# InkTime_V1.net
KiCad netlist of a schematic drawn in EAGLE
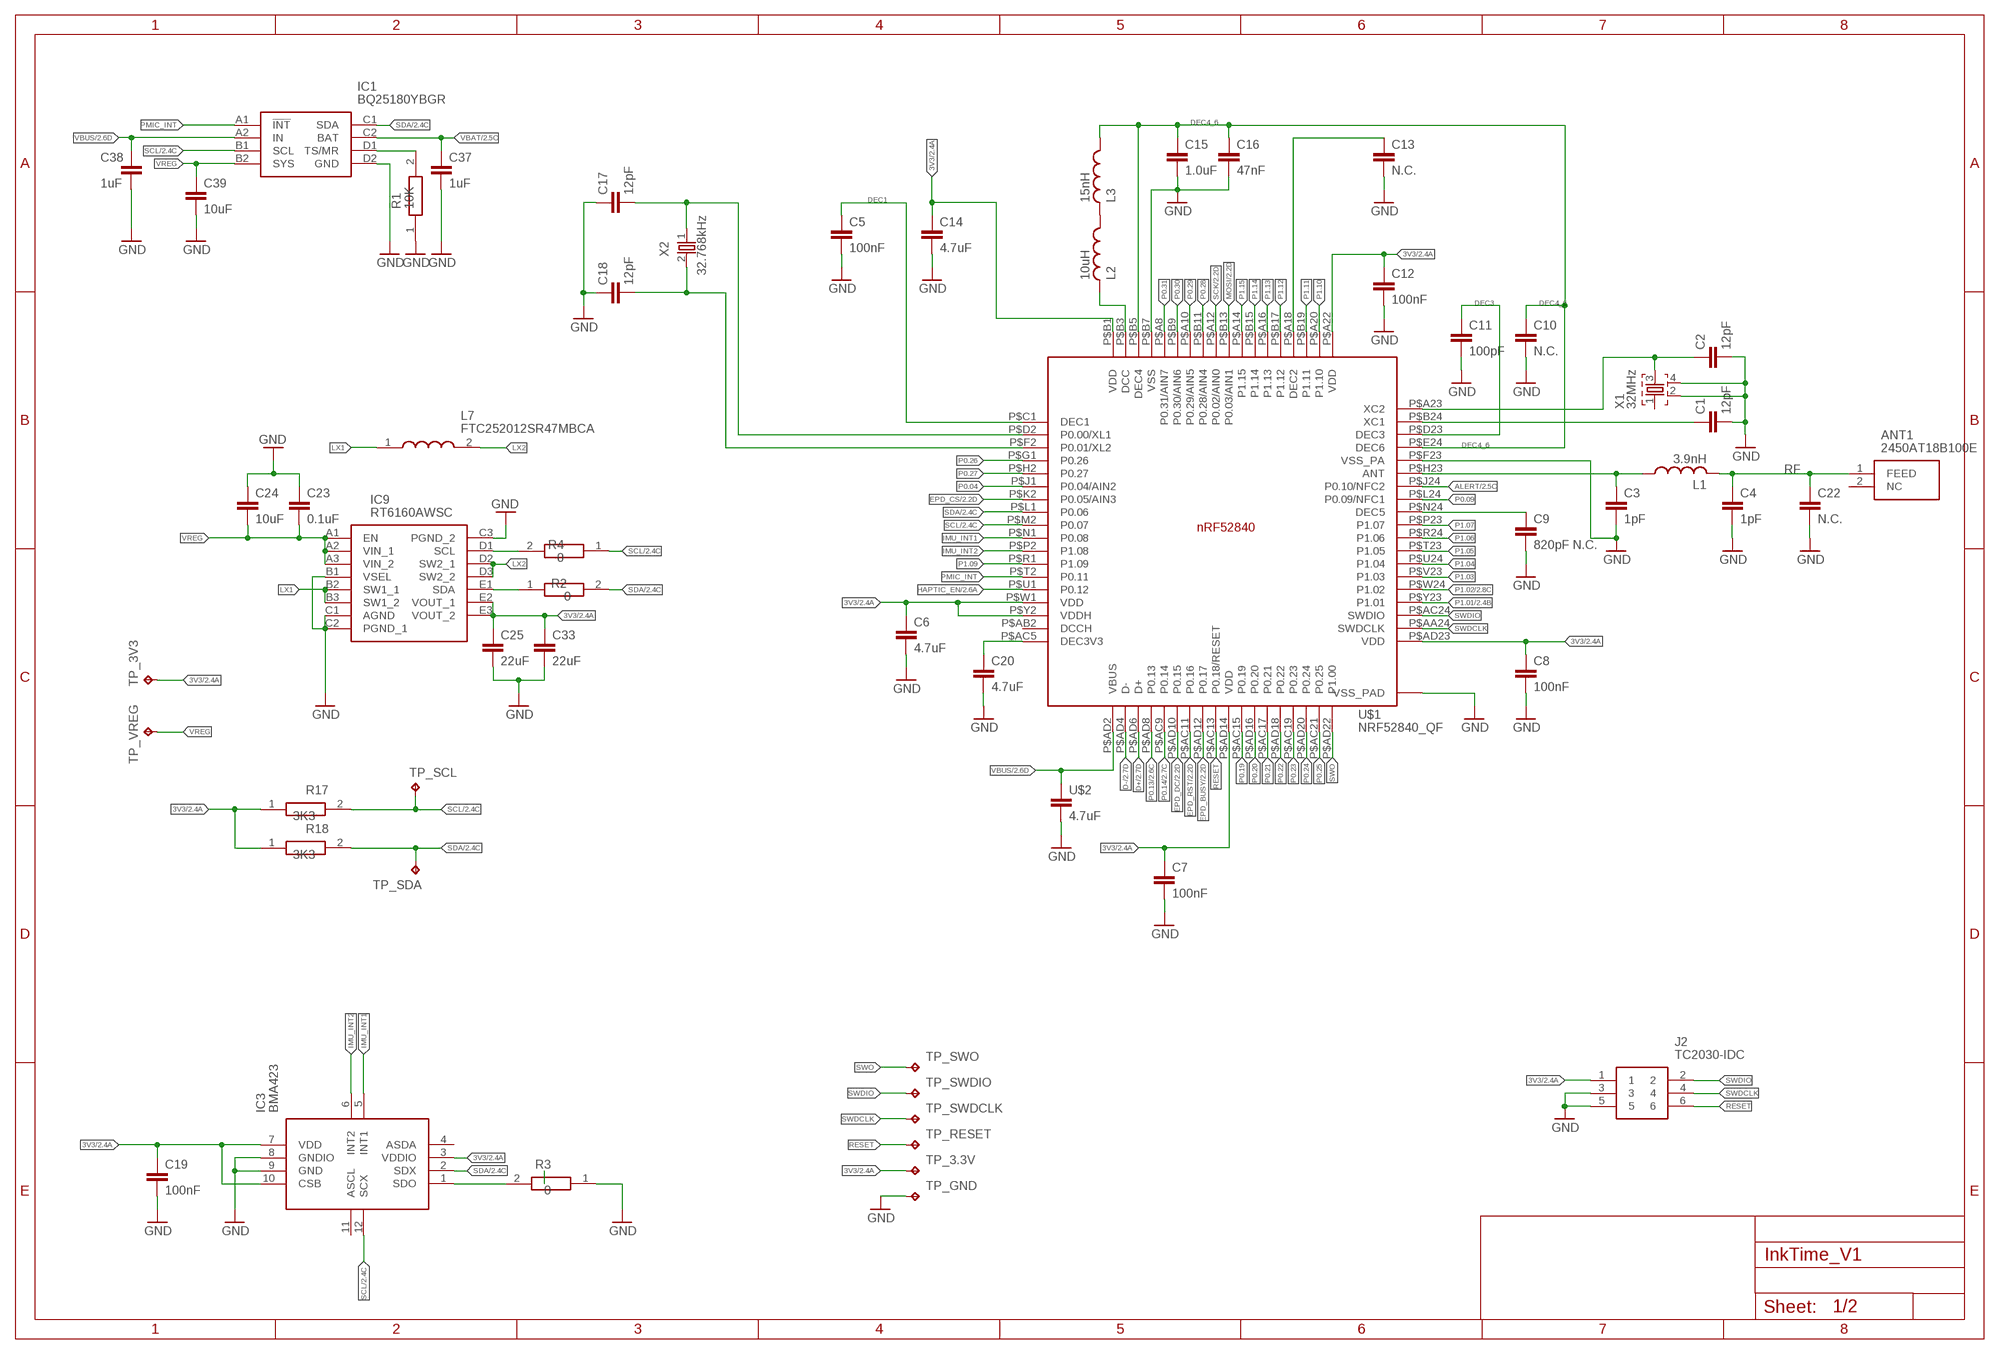
[diagram p0: schematic, sheet 1]
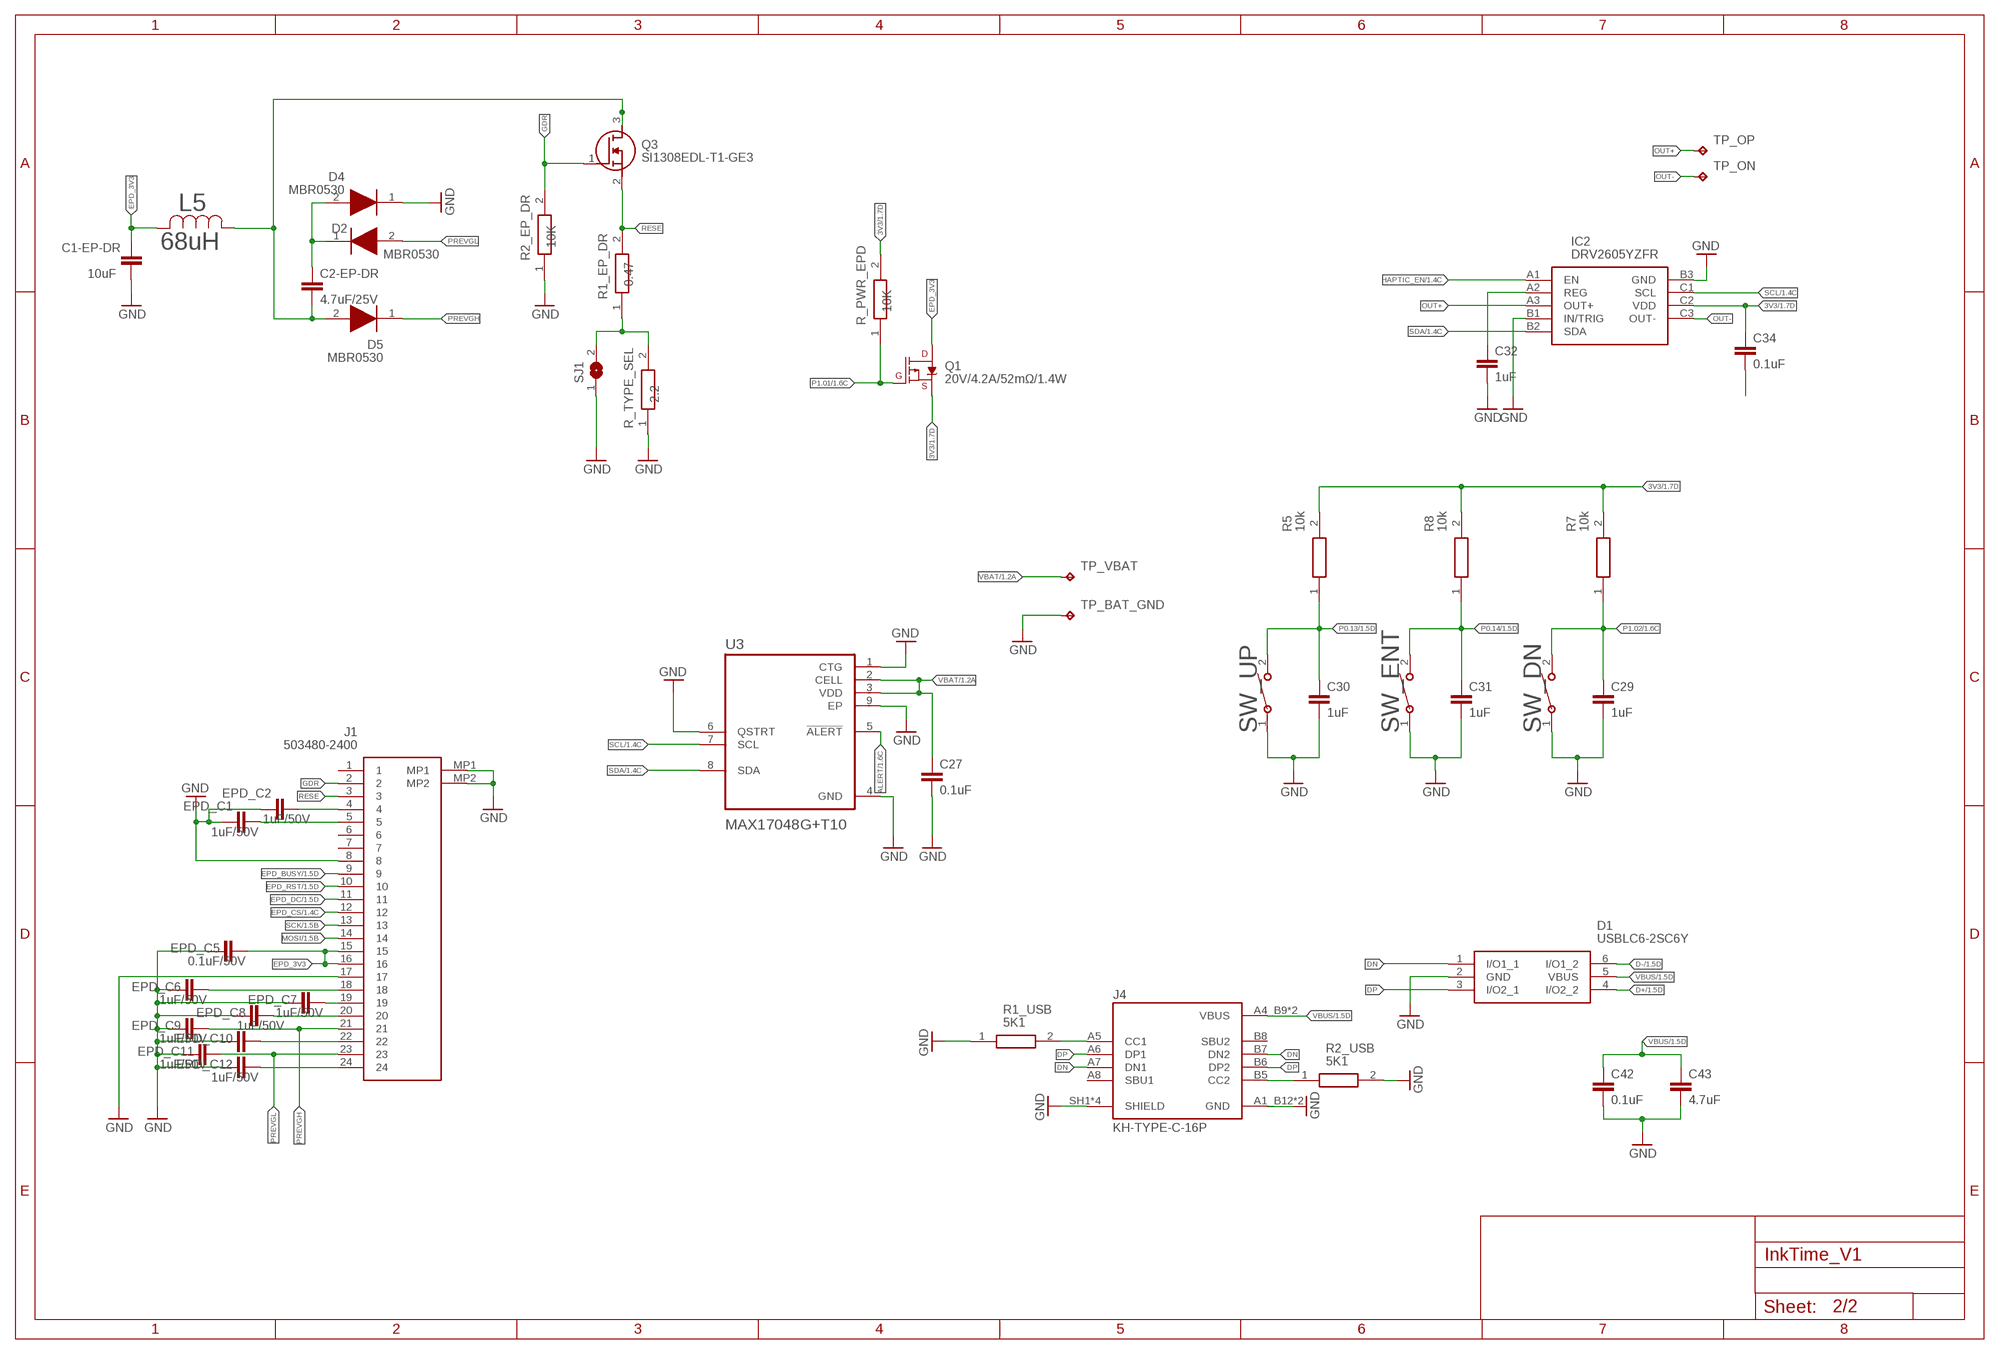
[diagram p1: schematic, sheet 2]

(export (version "E")
  (design (tool "Eeschema 10.0.6"))
  (components
    (comp (ref "ANT1")
      (value "2450AT18B100E")
      (footprint "eagle-import:2450AT18B100E_ANTC3216X140N")
      (fields (field (name "MOUSER_PART_NUMBER") "609-2450AT18B100E"))
      (libsource (lib "eagle-import") (part "2450AT18B100E_2450AT18B100E"))
    )
    (comp (ref "C1")
      (value "12pF")
      (footprint "eagle-import:NORDIC_NRF_3_RESC0201_L")
      (libsource (lib "eagle-import") (part "NORDIC_NRF_3_CAPACITOR_0201_L"))
    )
    (comp (ref "C2")
      (value "12pF")
      (footprint "eagle-import:NORDIC_NRF_3_RESC0201_L")
      (libsource (lib "eagle-import") (part "NORDIC_NRF_3_CAPACITOR_0201_L"))
    )
    (comp (ref "C3")
      (value "1pF")
      (footprint "eagle-import:NORDIC_NRF_3_RESC0201_L")
      (libsource (lib "eagle-import") (part "NORDIC_NRF_3_CAPACITOR_0201_L"))
    )
    (comp (ref "C4")
      (value "1pF")
      (footprint "eagle-import:NORDIC_NRF_3_RESC0201_L")
      (libsource (lib "eagle-import") (part "NORDIC_NRF_3_CAPACITOR_0201_L"))
    )
    (comp (ref "C5")
      (value "100nF")
      (footprint "eagle-import:NORDIC_NRF_3_RESC0201_L")
      (libsource (lib "eagle-import") (part "NORDIC_NRF_3_CAPACITOR_0201_L"))
    )
    (comp (ref "C6")
      (value "4.7uF")
      (footprint "eagle-import:NORDIC_NRF_3_RESC0201_L")
      (libsource (lib "eagle-import") (part "NORDIC_NRF_3_CAPACITOR_0201_L"))
    )
    (comp (ref "C7")
      (value "100nF")
      (footprint "eagle-import:NORDIC_NRF_3_RESC0201_L")
      (libsource (lib "eagle-import") (part "NORDIC_NRF_3_CAPACITOR_0201_L"))
    )
    (comp (ref "C8")
      (value "100nF")
      (footprint "eagle-import:NORDIC_NRF_3_RESC0201_L")
      (libsource (lib "eagle-import") (part "NORDIC_NRF_3_CAPACITOR_0201_L"))
    )
    (comp (ref "C9")
      (value "820pF N.C.")
      (footprint "eagle-import:NORDIC_NRF_3_RESC0201_L")
      (libsource (lib "eagle-import") (part "NORDIC_NRF_3_CAPACITOR_0201_L"))
    )
    (comp (ref "C10")
      (value "N.C.")
      (footprint "eagle-import:NORDIC_NRF_3_RESC0201_L")
      (libsource (lib "eagle-import") (part "NORDIC_NRF_3_CAPACITOR_0201_L"))
    )
    (comp (ref "C11")
      (value "100pF")
      (footprint "eagle-import:NORDIC_NRF_3_RESC0201_L")
      (libsource (lib "eagle-import") (part "NORDIC_NRF_3_CAPACITOR_0201_L"))
    )
    (comp (ref "C12")
      (value "100nF")
      (footprint "eagle-import:NORDIC_NRF_3_RESC0201_L")
      (libsource (lib "eagle-import") (part "NORDIC_NRF_3_CAPACITOR_0201_L"))
    )
    (comp (ref "C13")
      (value "N.C.")
      (footprint "eagle-import:NORDIC_NRF_3_RESC0201_L")
      (libsource (lib "eagle-import") (part "NORDIC_NRF_3_CAPACITOR_0201_L"))
    )
    (comp (ref "C14")
      (value "4.7uF")
      (footprint "eagle-import:NORDIC_NRF_3_RESC0201_L")
      (libsource (lib "eagle-import") (part "NORDIC_NRF_3_CAPACITOR_0201_L"))
    )
    (comp (ref "C15")
      (value "1.0uF")
      (footprint "eagle-import:NORDIC_NRF_3_RESC0201_L")
      (libsource (lib "eagle-import") (part "NORDIC_NRF_3_CAPACITOR_0201_L"))
    )
    (comp (ref "C16")
      (value "47nF")
      (footprint "eagle-import:NORDIC_NRF_3_RESC0201_L")
      (libsource (lib "eagle-import") (part "NORDIC_NRF_3_CAPACITOR_0201_L"))
    )
    (comp (ref "C17")
      (value "12pF")
      (footprint "eagle-import:NORDIC_NRF_3_RESC0201_L")
      (libsource (lib "eagle-import") (part "NORDIC_NRF_3_CAPACITOR_0201_L"))
    )
    (comp (ref "C18")
      (value "12pF")
      (footprint "eagle-import:NORDIC_NRF_3_RESC0201_L")
      (libsource (lib "eagle-import") (part "NORDIC_NRF_3_CAPACITOR_0201_L"))
    )
    (comp (ref "C19")
      (value "100nF")
      (footprint "eagle-import:NORDIC_NRF_3_RESC0201_L")
      (libsource (lib "eagle-import") (part "NORDIC_NRF_3_CAPACITOR_0201_L"))
    )
    (comp (ref "C20")
      (value "4.7uF")
      (footprint "eagle-import:NORDIC_NRF_3_RESC0201_L")
      (libsource (lib "eagle-import") (part "NORDIC_NRF_3_CAPACITOR_0201_L"))
    )
    (comp (ref "C22")
      (value "N.C.")
      (footprint "eagle-import:NORDIC_NRF_3_RESC0201_L")
      (libsource (lib "eagle-import") (part "NORDIC_NRF_3_CAPACITOR_0201_L"))
    )
    (comp (ref "C23")
      (value "0.1uF")
      (footprint "eagle-import:NORDIC_NRF_3_RESC0402_L")
      (libsource (lib "eagle-import") (part "NORDIC_NRF_3_CAPACITOR_0402_L"))
    )
    (comp (ref "C24")
      (value "10uF")
      (footprint "eagle-import:NORDIC_NRF_3_RESC0201_L")
      (libsource (lib "eagle-import") (part "NORDIC_NRF_3_CAPACITOR_0201_L"))
    )
    (comp (ref "C25")
      (value "22uF")
      (footprint "eagle-import:NORDIC_NRF_3_RESC0201_L")
      (libsource (lib "eagle-import") (part "NORDIC_NRF_3_CAPACITOR_0201_L"))
    )
    (comp (ref "C33")
      (value "22uF")
      (footprint "eagle-import:NORDIC_NRF_3_RESC0201_L")
      (libsource (lib "eagle-import") (part "NORDIC_NRF_3_CAPACITOR_0201_L"))
    )
    (comp (ref "C37")
      (value "1uF")
      (footprint "eagle-import:PERFECT_0402_0402")
      (libsource (lib "eagle-import") (part "PERFECT_0402_CAP_0402"))
    )
    (comp (ref "C38")
      (value "1uF")
      (footprint "eagle-import:NORDIC_NRF_3_RESC0402_L")
      (libsource (lib "eagle-import") (part "NORDIC_NRF_3_CAPACITOR_0402_L"))
    )
    (comp (ref "C39")
      (value "10uF")
      (footprint "eagle-import:NORDIC_NRF_3_RESC0201_L")
      (libsource (lib "eagle-import") (part "NORDIC_NRF_3_CAPACITOR_0201_L"))
    )
    (comp (ref "IC1")
      (value "BQ25180YBGR")
      (footprint "eagle-import:BQ25180YBGR_BGA8C40P2X4_100X155X50")
      (fields (field (name "MOUSER_PART_NUMBER") "595-BQ25180YBGR"))
      (libsource (lib "eagle-import") (part "BQ25180YBGR_BQ25180YBGR"))
    )
    (comp (ref "IC3")
      (value "BMA423")
      (footprint "eagle-import:BMA423_BMA423")
      (fields (field (name "MOUSER_PART_NUMBER") "262-BMA423"))
      (libsource (lib "eagle-import") (part "BMA423_BMA423"))
    )
    (comp (ref "IC9")
      (value "RT6160AWSC")
      (footprint "eagle-import:RT6160AWSC_BGA15C40P3X5_140X230X60")
      (fields (field (name "MOUSER_PART_NUMBER") "835-RT6160AWSC"))
      (libsource (lib "eagle-import") (part "RT6160AWSC_RT6160AWSC"))
    )
    (comp (ref "J2")
      (value "TC2030-IDC")
      (footprint "eagle-import:TC2030-IDC_TC2030IDC")
      (libsource (lib "eagle-import") (part "TC2030-IDC_TC2030-IDC"))
    )
    (comp (ref "L1")
      (value "3.9nH")
      (footprint "eagle-import:NORDIC_NRF_2_RESC0402_L")
      (libsource (lib "eagle-import") (part "NORDIC_NRF_2_INDUCTOR_0402_L"))
    )
    (comp (ref "L2")
      (value "10uH")
      (footprint "eagle-import:NORDIC_NRF_2_RESC0402_L")
      (libsource (lib "eagle-import") (part "NORDIC_NRF_2_INDUCTOR_0402_L"))
    )
    (comp (ref "L3")
      (value "15nH")
      (footprint "eagle-import:NORDIC_NRF_2_RESC0402_L")
      (libsource (lib "eagle-import") (part "NORDIC_NRF_2_INDUCTOR_0402_L"))
    )
    (comp (ref "L7")
      (value "FTC252012SR47MBCA")
      (footprint "eagle-import:MLP2016SR47MT0S1_INDC2016X100N")
      (libsource (lib "eagle-import") (part "MLP2016SR47MT0S1_FTC252012SR47MBCA"))
    )
    (comp (ref "R1")
      (value "10K")
      (footprint "eagle-import:CPF0201D7K68C1_0201")
      (libsource (lib "eagle-import") (part "CPF0201D7K68C1_CPF0201D7K68C1"))
    )
    (comp (ref "R2")
      (value "0")
      (footprint "eagle-import:CPF0201D7K68C1_0201")
      (libsource (lib "eagle-import") (part "CPF0201D7K68C1_CPF0201D7K68C1"))
    )
    (comp (ref "R3")
      (value "0")
      (footprint "eagle-import:CPF0201D7K68C1_0201")
      (libsource (lib "eagle-import") (part "CPF0201D7K68C1_CPF0201D7K68C1"))
    )
    (comp (ref "R4")
      (value "0")
      (footprint "eagle-import:CPF0201D7K68C1_0201")
      (libsource (lib "eagle-import") (part "CPF0201D7K68C1_CPF0201D7K68C1"))
    )
    (comp (ref "R17")
      (value "3K3")
      (footprint "eagle-import:CPF0201D7K68C1_0201")
      (libsource (lib "eagle-import") (part "CPF0201D7K68C1_CPF0201D7K68C1"))
    )
    (comp (ref "R18")
      (value "3K3")
      (footprint "eagle-import:CPF0201D7K68C1_0201")
      (libsource (lib "eagle-import") (part "CPF0201D7K68C1_CPF0201D7K68C1"))
    )
    (comp (ref "TP_3.3V")
      (value "HECTOR_WATCH_1_TPTP20R")
      (footprint "eagle-import:HECTOR_WATCH_1_TP20R")
      (libsource (lib "eagle-import") (part "HECTOR_WATCH_1_TPTP20R"))
    )
    (comp (ref "TP_3V3")
      (value "HECTOR_WATCH_1_TPTP20R")
      (footprint "eagle-import:HECTOR_WATCH_1_TP20R")
      (libsource (lib "eagle-import") (part "HECTOR_WATCH_1_TPTP20R"))
    )
    (comp (ref "TP_GND")
      (value "HECTOR_WATCH_1_TPTP20R")
      (footprint "eagle-import:HECTOR_WATCH_1_TP20R")
      (libsource (lib "eagle-import") (part "HECTOR_WATCH_1_TPTP20R"))
    )
    (comp (ref "TP_RESET")
      (value "HECTOR_WATCH_1_TPTP20R")
      (footprint "eagle-import:HECTOR_WATCH_1_TP20R")
      (libsource (lib "eagle-import") (part "HECTOR_WATCH_1_TPTP20R"))
    )
    (comp (ref "TP_SCL")
      (value "HECTOR_WATCH_1_TPTP20R")
      (footprint "eagle-import:HECTOR_WATCH_1_TP20R")
      (libsource (lib "eagle-import") (part "HECTOR_WATCH_1_TPTP20R"))
    )
    (comp (ref "TP_SDA")
      (value "HECTOR_WATCH_1_TPTP20R")
      (footprint "eagle-import:HECTOR_WATCH_1_TP20R")
      (libsource (lib "eagle-import") (part "HECTOR_WATCH_1_TPTP20R"))
    )
    (comp (ref "TP_SWDCLK")
      (value "HECTOR_WATCH_1_TPTP20R")
      (footprint "eagle-import:HECTOR_WATCH_1_TP20R")
      (libsource (lib "eagle-import") (part "HECTOR_WATCH_1_TPTP20R"))
    )
    (comp (ref "TP_SWDIO")
      (value "HECTOR_WATCH_1_TPTP20R")
      (footprint "eagle-import:HECTOR_WATCH_1_TP20R")
      (libsource (lib "eagle-import") (part "HECTOR_WATCH_1_TPTP20R"))
    )
    (comp (ref "TP_SWO")
      (value "HECTOR_WATCH_1_TPTP20R")
      (footprint "eagle-import:HECTOR_WATCH_1_TP20R")
      (libsource (lib "eagle-import") (part "HECTOR_WATCH_1_TPTP20R"))
    )
    (comp (ref "TP_VREG")
      (value "HECTOR_WATCH_1_TPTP20R")
      (footprint "eagle-import:HECTOR_WATCH_1_TP20R")
      (libsource (lib "eagle-import") (part "HECTOR_WATCH_1_TPTP20R"))
    )
    (comp (ref "U$1")
      (value "NRF52840_QF")
      (footprint "eagle-import:NORDIC_NRF_4_AQFN50P700X700X85_HS-74N")
      (libsource (lib "eagle-import") (part "NORDIC_NRF_4_NRF52840_QF"))
    )
    (comp (ref "U$2")
      (value "4.7uF")
      (footprint "eagle-import:NORDIC_NRF_3_RESC0201_L")
      (libsource (lib "eagle-import") (part "NORDIC_NRF_3_CAPACITOR_0201_L"))
    )
    (comp (ref "X1")
      (value "32MHz")
      (footprint "eagle-import:NORDIC_NRF_BT-XTAL_2016_N")
      (libsource (lib "eagle-import") (part "NORDIC_NRF_XTAL_32MHZ"))
    )
    (comp (ref "X2")
      (value "32.768kHz")
      (footprint "eagle-import:NORDIC_NRF_1_XTAL_3215_N")
      (libsource (lib "eagle-import") (part "NORDIC_NRF_1_XTAL_32KHZ"))
    )
    (comp (ref "C1-EP-DR")
      (value "10uF")
      (footprint "eagle-import:NORDIC_NRF_3_RESC0201_L")
      (libsource (lib "eagle-import") (part "NORDIC_NRF_3_CAPACITOR_0201_L"))
    )
    (comp (ref "C2-EP-DR")
      (value "4.7uF/25V")
      (footprint "eagle-import:NORDIC_NRF_3_RESC0201_L")
      (libsource (lib "eagle-import") (part "NORDIC_NRF_3_CAPACITOR_0201_L"))
    )
    (comp (ref "C27")
      (value "0.1uF")
      (footprint "eagle-import:NORDIC_NRF_3_RESC0402_L")
      (libsource (lib "eagle-import") (part "NORDIC_NRF_3_CAPACITOR_0402_L"))
    )
    (comp (ref "C29")
      (value "1uF")
      (footprint "eagle-import:NORDIC_NRF_3_RESC0402_L")
      (libsource (lib "eagle-import") (part "NORDIC_NRF_3_CAPACITOR_0402_L"))
    )
    (comp (ref "C30")
      (value "1uF")
      (footprint "eagle-import:NORDIC_NRF_3_RESC0402_L")
      (libsource (lib "eagle-import") (part "NORDIC_NRF_3_CAPACITOR_0402_L"))
    )
    (comp (ref "C31")
      (value "1uF")
      (footprint "eagle-import:NORDIC_NRF_3_RESC0402_L")
      (libsource (lib "eagle-import") (part "NORDIC_NRF_3_CAPACITOR_0402_L"))
    )
    (comp (ref "C32")
      (value "1uF")
      (footprint "eagle-import:NORDIC_NRF_3_RESC0402_L")
      (libsource (lib "eagle-import") (part "NORDIC_NRF_3_CAPACITOR_0402_L"))
    )
    (comp (ref "C34")
      (value "0.1uF")
      (footprint "eagle-import:NORDIC_NRF_3_RESC0402_L")
      (libsource (lib "eagle-import") (part "NORDIC_NRF_3_CAPACITOR_0402_L"))
    )
    (comp (ref "C42")
      (value "0.1uF")
      (footprint "eagle-import:NORDIC_NRF_3_RESC0402_L")
      (libsource (lib "eagle-import") (part "NORDIC_NRF_3_CAPACITOR_0402_L"))
    )
    (comp (ref "C43")
      (value "4.7uF")
      (footprint "eagle-import:NORDIC_NRF_3_RESC0201_L")
      (libsource (lib "eagle-import") (part "NORDIC_NRF_3_CAPACITOR_0201_L"))
    )
    (comp (ref "D1")
      (value "USBLC6-2SC6Y")
      (footprint "eagle-import:ESP32_C6_LIBRARY_3_SOT95P280X145-6N")
      (fields (field (name "MF") "STMicroelectronics"))
      (libsource (lib "eagle-import") (part "ESP32_C6_LIBRARY_3_USBLC6-2SC6Y"))
    )
    (comp (ref "D2")
      (value "MBR0530")
      (footprint "eagle-import:ESP32_C6_LIBRARY_5_SOD3716X135N")
      (fields (field (name "MF") "ON Semiconductor"))
      (libsource (lib "eagle-import") (part "ESP32_C6_LIBRARY_5_MBR0530"))
    )
    (comp (ref "D4")
      (value "MBR0530")
      (footprint "eagle-import:ESP32_C6_LIBRARY_5_SOD3716X135N")
      (fields (field (name "MF") "ON Semiconductor"))
      (libsource (lib "eagle-import") (part "ESP32_C6_LIBRARY_5_MBR0530"))
    )
    (comp (ref "D5")
      (value "MBR0530")
      (footprint "eagle-import:ESP32_C6_LIBRARY_5_SOD3716X135N")
      (fields (field (name "MF") "ON Semiconductor"))
      (libsource (lib "eagle-import") (part "ESP32_C6_LIBRARY_5_MBR0530"))
    )
    (comp (ref "EPD_C1")
      (value "1uF/50V")
      (footprint "eagle-import:NORDIC_NRF_3_RESC0201_L")
      (libsource (lib "eagle-import") (part "NORDIC_NRF_3_CAPACITOR_0201_L"))
    )
    (comp (ref "EPD_C2")
      (value "1uF/50V")
      (footprint "eagle-import:NORDIC_NRF_3_RESC0201_L")
      (libsource (lib "eagle-import") (part "NORDIC_NRF_3_CAPACITOR_0201_L"))
    )
    (comp (ref "EPD_C5")
      (value "0.1uF/50V")
      (footprint "eagle-import:NORDIC_NRF_3_RESC0201_L")
      (libsource (lib "eagle-import") (part "NORDIC_NRF_3_CAPACITOR_0201_L"))
    )
    (comp (ref "EPD_C6")
      (value "1uF/50V")
      (footprint "eagle-import:NORDIC_NRF_3_RESC0201_L")
      (libsource (lib "eagle-import") (part "NORDIC_NRF_3_CAPACITOR_0201_L"))
    )
    (comp (ref "EPD_C7")
      (value "1uF/50V")
      (footprint "eagle-import:NORDIC_NRF_3_RESC0201_L")
      (libsource (lib "eagle-import") (part "NORDIC_NRF_3_CAPACITOR_0201_L"))
    )
    (comp (ref "EPD_C8")
      (value "1uF/50V")
      (footprint "eagle-import:NORDIC_NRF_3_RESC0201_L")
      (libsource (lib "eagle-import") (part "NORDIC_NRF_3_CAPACITOR_0201_L"))
    )
    (comp (ref "EPD_C9")
      (value "1uF/50V")
      (footprint "eagle-import:NORDIC_NRF_3_RESC0201_L")
      (libsource (lib "eagle-import") (part "NORDIC_NRF_3_CAPACITOR_0201_L"))
    )
    (comp (ref "EPD_C10")
      (value "NORDIC_NRF_3_CAPACITOR_0201_L")
      (footprint "eagle-import:NORDIC_NRF_3_RESC0201_L")
      (libsource (lib "eagle-import") (part "NORDIC_NRF_3_CAPACITOR_0201_L"))
    )
    (comp (ref "EPD_C11")
      (value "1uF/50V")
      (footprint "eagle-import:NORDIC_NRF_3_RESC0201_L")
      (libsource (lib "eagle-import") (part "NORDIC_NRF_3_CAPACITOR_0201_L"))
    )
    (comp (ref "EPD_C12")
      (value "1uF/50V")
      (footprint "eagle-import:NORDIC_NRF_3_RESC0201_L")
      (libsource (lib "eagle-import") (part "NORDIC_NRF_3_CAPACITOR_0201_L"))
    )
    (comp (ref "IC2")
      (value "DRV2605YZFR")
      (footprint "eagle-import:DRV2605YZFR_BGA9C50P3X3_144X144X62")
      (libsource (lib "eagle-import") (part "DRV2605YZFR_DRV2605YZFR"))
    )
    (comp (ref "J1")
      (value "503480-2400")
      (footprint "eagle-import:503480-2400_5034802400")
      (fields (field (name "MOUSER_PART_NUMBER") "538-503480-2400"))
      (libsource (lib "eagle-import") (part "503480-2400_503480-2400"))
    )
    (comp (ref "J4")
      (value "KH-TYPE-C-16P")
      (footprint "eagle-import:KH-TYPE-C-16P_KINGHELM_KH-TYPE-C-16P")
      (fields (field (name "MF") "kinghelm"))
      (libsource (lib "eagle-import") (part "KH-TYPE-C-16P_KH-TYPE-C-16P"))
    )
    (comp (ref "L5")
      (value "68uH")
      (footprint "eagle-import:ESP32_C6_LIBRARY_2_IND_4828-WE-TPC_WRE")
      (fields
        (field (name "MANUFACTURER_PART_NUMBER") "744043680")
        (field (name "COPYRIGHT") "Copyright (C) 2024 Ultra Librarian. All rights reserved.")
      )
      (libsource (lib "eagle-import") (part "ESP32_C6_LIBRARY_2_744043680IND_4828-WE-TPC_WRE"))
    )
    (comp (ref "Q1")
      (value "20V/4.2A/52mΩ/1.4W")
      (footprint "eagle-import:ESP32_C6_LIBRARY_4_ESP32_C6_LIBRARY_4_ESP32_C6_LIBRARY_4_ESP32_C6_LIBRARY_4_ESP32_WROVER_SPARKFUN-DISCRETESEMI_SOT23-3")
      (libsource (lib "eagle-import") (part "ESP32_C6_LIBRARY_4_ESP32_WROVER_SPARKFUN-DISCRETESEMI_MOSFET_PCH-DMG2305UX-7"))
    )
    (comp (ref "Q3")
      (value "SI1308EDL-T1-GE3")
      (footprint "eagle-import:ESP32_C6_LIBRARY_6_SOT65P210X110-3N")
      (fields (field (name "MF") "Vishay Siliconix"))
      (libsource (lib "eagle-import") (part "ESP32_C6_LIBRARY_6_SI1308EDL-T1-GE3"))
    )
    (comp (ref "R1_EP_DR")
      (value "0.47")
      (footprint "eagle-import:CPF0201D7K68C1_0201")
      (libsource (lib "eagle-import") (part "CPF0201D7K68C1_CPF0201D7K68C1"))
    )
    (comp (ref "R1_USB")
      (value "5K1")
      (footprint "eagle-import:CPF0201D7K68C1_0201")
      (libsource (lib "eagle-import") (part "CPF0201D7K68C1_CPF0201D7K68C1"))
    )
    (comp (ref "R2_EP_DR")
      (value "10K")
      (footprint "eagle-import:ERA-1AEB3401C_0201")
      (libsource (lib "eagle-import") (part "ERA-1AEB3401C_CPF0201D7K68C1"))
    )
    (comp (ref "R2_USB")
      (value "5K1")
      (footprint "eagle-import:CPF0201D7K68C1_0201")
      (libsource (lib "eagle-import") (part "CPF0201D7K68C1_CPF0201D7K68C1"))
    )
    (comp (ref "R5")
      (value "10k")
      (footprint "eagle-import:CPF0201D7K68C1_0201")
      (libsource (lib "eagle-import") (part "CPF0201D7K68C1_CPF0201D7K68C1"))
    )
    (comp (ref "R7")
      (value "10k")
      (footprint "eagle-import:CPF0201D7K68C1_0201")
      (libsource (lib "eagle-import") (part "CPF0201D7K68C1_CPF0201D7K68C1"))
    )
    (comp (ref "R8")
      (value "10k")
      (footprint "eagle-import:CPF0201D7K68C1_0201")
      (libsource (lib "eagle-import") (part "CPF0201D7K68C1_CPF0201D7K68C1"))
    )
    (comp (ref "R_PWR_EPD")
      (value "10K")
      (footprint "eagle-import:CPF0201D7K68C1_0201")
      (libsource (lib "eagle-import") (part "CPF0201D7K68C1_CPF0201D7K68C1"))
    )
    (comp (ref "R_TYPE_SEL")
      (value "2.2")
      (footprint "eagle-import:CPF0201D7K68C1_0201")
      (libsource (lib "eagle-import") (part "CPF0201D7K68C1_CPF0201D7K68C1"))
    )
    (comp (ref "SJ1")
      (value "ESP32_C6_LIBRARY_7_JUMPER_SJ")
      (footprint "eagle-import:ESP32_C6_LIBRARY_7_JUMPER_SJ")
      (libsource (lib "eagle-import") (part "ESP32_C6_LIBRARY_7_JUMPER_SJ"))
    )
    (comp (ref "SW_DN")
      (value "2025-10-22_07-23-44_LIBRARY_EVP-AKE31ASW_EVP-AKE31A_PAN")
      (footprint "eagle-import:2025-10-22_07-23-44_LIBRARY_SW_EVP-AKE31A_PAN")
      (fields
        (field (name "MANUFACTURER_PART_NUMBER") "EVP-AKE31A")
        (field (name "COPYRIGHT") "Copyright (C) 2025 Ultra Librarian. All rights reserved.")
      )
      (libsource (lib "eagle-import") (part "2025-10-22_07-23-44_LIBRARY_EVP-AKE31ASW_EVP-AKE31A_PAN"))
    )
    (comp (ref "SW_ENT")
      (value "2025-10-22_07-23-44_LIBRARY_EVP-AKE31ASW_EVP-AKE31A_PAN")
      (footprint "eagle-import:2025-10-22_07-23-44_LIBRARY_SW_EVP-AKE31A_PAN")
      (fields
        (field (name "MANUFACTURER_PART_NUMBER") "EVP-AKE31A")
        (field (name "COPYRIGHT") "Copyright (C) 2025 Ultra Librarian. All rights reserved.")
      )
      (libsource (lib "eagle-import") (part "2025-10-22_07-23-44_LIBRARY_EVP-AKE31ASW_EVP-AKE31A_PAN"))
    )
    (comp (ref "SW_UP")
      (value "2025-10-22_07-23-44_LIBRARY_EVP-AKE31ASW_EVP-AKE31A_PAN")
      (footprint "eagle-import:2025-10-22_07-23-44_LIBRARY_SW_EVP-AKE31A_PAN")
      (fields
        (field (name "MANUFACTURER_PART_NUMBER") "EVP-AKE31A")
        (field (name "COPYRIGHT") "Copyright (C) 2025 Ultra Librarian. All rights reserved.")
      )
      (libsource (lib "eagle-import") (part "2025-10-22_07-23-44_LIBRARY_EVP-AKE31ASW_EVP-AKE31A_PAN"))
    )
    (comp (ref "TP_BAT_GND")
      (value "HECTOR_WATCH_1_TPTP20R")
      (footprint "eagle-import:HECTOR_WATCH_1_TP20R")
      (libsource (lib "eagle-import") (part "HECTOR_WATCH_1_TPTP20R"))
    )
    (comp (ref "TP_ON")
      (value "HECTOR_WATCH_1_TPTP20R")
      (footprint "eagle-import:HECTOR_WATCH_1_TP20R")
      (libsource (lib "eagle-import") (part "HECTOR_WATCH_1_TPTP20R"))
    )
    (comp (ref "TP_OP")
      (value "HECTOR_WATCH_1_TPTP20R")
      (footprint "eagle-import:HECTOR_WATCH_1_TP20R")
      (libsource (lib "eagle-import") (part "HECTOR_WATCH_1_TPTP20R"))
    )
    (comp (ref "TP_VBAT")
      (value "HECTOR_WATCH_1_TPTP20R")
      (footprint "eagle-import:HECTOR_WATCH_1_TP20R")
      (libsource (lib "eagle-import") (part "HECTOR_WATCH_1_TPTP20R"))
    )
    (comp (ref "U3")
      (value "MAX17048G+T10")
      (footprint "eagle-import:ESP32_C6_LIBRARY_SON50P200X200X80-9N")
      (fields (field (name "MF") "Analog Devices"))
      (libsource (lib "eagle-import") (part "ESP32_C6_LIBRARY_MAX17048G+T10"))
    )
  )
  (nets
    (net (code "1") (name "3V3{slash}1.7D") (class "Default")
      (node (ref "C34") (pin "1") (pinfunction "1_1") (pintype "passive"))
      (node (ref "IC2") (pin "C2") (pinfunction "VDD_C2") (pintype "bidirectional"))
      (node (ref "Q1") (pin "2") (pinfunction "S_2") (pintype "bidirectional"))
      (node (ref "R5") (pin "2") (pinfunction "2_2") (pintype "bidirectional"))
      (node (ref "R7") (pin "2") (pinfunction "2_2") (pintype "bidirectional"))
      (node (ref "R8") (pin "2") (pinfunction "2_2") (pintype "bidirectional"))
      (node (ref "R_PWR_EPD") (pin "2") (pinfunction "2_2") (pintype "bidirectional"))
    )
    (net (code "2") (name "3V3{slash}2.4A") (class "Default")
      (node (ref "C12") (pin "1") (pinfunction "1_1") (pintype "passive"))
      (node (ref "C14") (pin "1") (pinfunction "1_1") (pintype "passive"))
      (node (ref "C19") (pin "1") (pinfunction "1_1") (pintype "passive"))
      (node (ref "C25") (pin "1") (pinfunction "1_1") (pintype "passive"))
      (node (ref "C33") (pin "1") (pinfunction "1_1") (pintype "passive"))
      (node (ref "C6") (pin "1") (pinfunction "1_1") (pintype "passive"))
      (node (ref "C7") (pin "1") (pinfunction "1_1") (pintype "passive"))
      (node (ref "C8") (pin "1") (pinfunction "1_1") (pintype "passive"))
      (node (ref "IC3") (pin "10") (pinfunction "CSB_10") (pintype "bidirectional"))
      (node (ref "IC3") (pin "3") (pinfunction "VDDIO_3") (pintype "bidirectional"))
      (node (ref "IC3") (pin "7") (pinfunction "VDD_7") (pintype "bidirectional"))
      (node (ref "IC9") (pin "E2") (pinfunction "VOUT_1_E2") (pintype "bidirectional"))
      (node (ref "IC9") (pin "E3") (pinfunction "VOUT_2_E3") (pintype "bidirectional"))
      (node (ref "J2") (pin "1") (pinfunction "1_1") (pintype "bidirectional"))
      (node (ref "R17") (pin "1") (pinfunction "1_1") (pintype "bidirectional"))
      (node (ref "R18") (pin "1") (pinfunction "1_1") (pintype "bidirectional"))
      (node (ref "TP_3.3V") (pin "TP") (pinfunction "TP_TP") (pintype "input"))
      (node (ref "TP_3V3") (pin "TP") (pinfunction "TP_TP") (pintype "input"))
      (node (ref "U$1") (pin "P$A22") (pinfunction "VDD_P$A22") (pintype "power_in"))
      (node (ref "U$1") (pin "P$AD14") (pinfunction "VDD_P$AD14") (pintype "power_in"))
      (node (ref "U$1") (pin "P$AD23") (pinfunction "VDD_P$AD23") (pintype "power_in"))
      (node (ref "U$1") (pin "P$B1") (pinfunction "VDD_P$B1") (pintype "power_in"))
      (node (ref "U$1") (pin "P$W1") (pinfunction "VDD_P$W1") (pintype "power_in"))
      (node (ref "U$1") (pin "P$Y2") (pinfunction "VDDH_P$Y2") (pintype "power_in"))
    )
    (net (code "3") (name "ALERT{slash}1.6C") (class "Default")
      (node (ref "U3") (pin "5") (pinfunction "~{ALERT}_5") (pintype "output"))
    )
    (net (code "4") (name "ALERT{slash}2.5C") (class "Default")
      (node (ref "U$1") (pin "P$J24") (pinfunction "P0.10/NFC2_P$J24") (pintype "bidirectional"))
    )
    (net (code "5") (name "D+{slash}1.5D") (class "Default")
      (node (ref "D1") (pin "4") (pinfunction "I/O2_2_4") (pintype "bidirectional"))
    )
    (net (code "6") (name "D+{slash}2.7D") (class "Default")
      (node (ref "U$1") (pin "P$AD6") (pinfunction "D+_P$AD6") (pintype "bidirectional"))
    )
    (net (code "7") (name "D-{slash}1.5D") (class "Default")
      (node (ref "D1") (pin "6") (pinfunction "I/O1_2_6") (pintype "bidirectional"))
    )
    (net (code "8") (name "D-{slash}2.7D") (class "Default")
      (node (ref "U$1") (pin "P$AD4") (pinfunction "D-_P$AD4") (pintype "bidirectional"))
    )
    (net (code "9") (name "DEC1") (class "Default")
      (node (ref "C5") (pin "1") (pinfunction "1_1") (pintype "passive"))
      (node (ref "U$1") (pin "P$C1") (pinfunction "DEC1_P$C1") (pintype "power_in"))
    )
    (net (code "10") (name "DEC3") (class "Default")
      (node (ref "C11") (pin "1") (pinfunction "1_1") (pintype "passive"))
      (node (ref "U$1") (pin "P$D23") (pinfunction "DEC3_P$D23") (pintype "bidirectional"))
    )
    (net (code "11") (name "DEC4_6") (class "Default")
      (node (ref "C10") (pin "1") (pinfunction "1_1") (pintype "passive"))
      (node (ref "C15") (pin "1") (pinfunction "1_1") (pintype "passive"))
      (node (ref "C16") (pin "1") (pinfunction "1_1") (pintype "passive"))
      (node (ref "L3") (pin "1") (pinfunction "1_1") (pintype "passive"))
      (node (ref "U$1") (pin "P$B5") (pinfunction "DEC4_P$B5") (pintype "power_in"))
      (node (ref "U$1") (pin "P$E24") (pinfunction "DEC6_P$E24") (pintype "bidirectional"))
    )
    (net (code "12") (name "DN") (class "Default")
      (node (ref "D1") (pin "1") (pinfunction "I/O1_1_1") (pintype "bidirectional"))
      (node (ref "J4") (pin "A7") (pinfunction "DN1_A7") (pintype "bidirectional"))
      (node (ref "J4") (pin "B7") (pinfunction "DN2_B7") (pintype "bidirectional"))
    )
    (net (code "13") (name "DP") (class "Default")
      (node (ref "D1") (pin "3") (pinfunction "I/O2_1_3") (pintype "bidirectional"))
      (node (ref "J4") (pin "A6") (pinfunction "DP1_A6") (pintype "bidirectional"))
      (node (ref "J4") (pin "B6") (pinfunction "DP2_B6") (pintype "bidirectional"))
    )
    (net (code "14") (name "EPD_3V3") (class "Default")
      (node (ref "C1-EP-DR") (pin "1") (pinfunction "1_1") (pintype "passive"))
      (node (ref "EPD_C5") (pin "2") (pinfunction "2_2") (pintype "passive"))
      (node (ref "J1") (pin "15") (pinfunction "15_15") (pintype "bidirectional"))
      (node (ref "J1") (pin "16") (pinfunction "16_16") (pintype "bidirectional"))
      (node (ref "L5") (pin "2") (pinfunction "2_2") (pintype "passive"))
      (node (ref "Q1") (pin "3") (pinfunction "D_3") (pintype "bidirectional"))
    )
    (net (code "15") (name "EPD_BUSY{slash}1.5D") (class "Default")
      (node (ref "J1") (pin "9") (pinfunction "9_9") (pintype "bidirectional"))
    )
    (net (code "16") (name "EPD_BUSY{slash}2.2D") (class "Default")
      (node (ref "U$1") (pin "P$AD12") (pinfunction "P0.17_P$AD12") (pintype "bidirectional"))
    )
    (net (code "17") (name "EPD_CS{slash}1.4C") (class "Default")
      (node (ref "J1") (pin "12") (pinfunction "12_12") (pintype "bidirectional"))
    )
    (net (code "18") (name "EPD_CS{slash}2.2D") (class "Default")
      (node (ref "U$1") (pin "P$K2") (pinfunction "P0.05/AIN3_P$K2") (pintype "bidirectional"))
    )
    (net (code "19") (name "EPD_DC{slash}1.5D") (class "Default")
      (node (ref "J1") (pin "11") (pinfunction "11_11") (pintype "bidirectional"))
    )
    (net (code "20") (name "EPD_DC{slash}2.2D") (class "Default")
      (node (ref "U$1") (pin "P$AD10") (pinfunction "P0.15_P$AD10") (pintype "bidirectional"))
    )
    (net (code "21") (name "EPD_RST{slash}1.5D") (class "Default")
      (node (ref "J1") (pin "10") (pinfunction "10_10") (pintype "bidirectional"))
    )
    (net (code "22") (name "EPD_RST{slash}2.2D") (class "Default")
      (node (ref "U$1") (pin "P$AC11") (pinfunction "P0.16_P$AC11") (pintype "bidirectional"))
    )
    (net (code "23") (name "GDR") (class "Default")
      (node (ref "J1") (pin "2") (pinfunction "2_2") (pintype "bidirectional"))
      (node (ref "Q3") (pin "1") (pinfunction "G_1") (pintype "bidirectional"))
      (node (ref "R2_EP_DR") (pin "2") (pinfunction "2_2") (pintype "bidirectional"))
    )
    (net (code "24") (name "GND") (class "Default")
      (node (ref "C1") (pin "2") (pinfunction "2_2") (pintype "passive"))
      (node (ref "C1-EP-DR") (pin "2") (pinfunction "2_2") (pintype "passive"))
      (node (ref "C10") (pin "2") (pinfunction "2_2") (pintype "passive"))
      (node (ref "C11") (pin "2") (pinfunction "2_2") (pintype "passive"))
      (node (ref "C12") (pin "2") (pinfunction "2_2") (pintype "passive"))
      (node (ref "C13") (pin "2") (pinfunction "2_2") (pintype "passive"))
      (node (ref "C14") (pin "2") (pinfunction "2_2") (pintype "passive"))
      (node (ref "C15") (pin "2") (pinfunction "2_2") (pintype "passive"))
      (node (ref "C16") (pin "2") (pinfunction "2_2") (pintype "passive"))
      (node (ref "C17") (pin "1") (pinfunction "1_1") (pintype "passive"))
      (node (ref "C18") (pin "1") (pinfunction "1_1") (pintype "passive"))
      (node (ref "C19") (pin "2") (pinfunction "2_2") (pintype "passive"))
      (node (ref "C2") (pin "2") (pinfunction "2_2") (pintype "passive"))
      (node (ref "C20") (pin "2") (pinfunction "2_2") (pintype "passive"))
      (node (ref "C22") (pin "2") (pinfunction "2_2") (pintype "passive"))
      (node (ref "C23") (pin "1") (pinfunction "1_1") (pintype "passive"))
      (node (ref "C24") (pin "1") (pinfunction "1_1") (pintype "passive"))
      (node (ref "C25") (pin "2") (pinfunction "2_2") (pintype "passive"))
      (node (ref "C27") (pin "2") (pinfunction "2_2") (pintype "passive"))
      (node (ref "C29") (pin "2") (pinfunction "2_2") (pintype "passive"))
      (node (ref "C3") (pin "2") (pinfunction "2_2") (pintype "passive"))
      (node (ref "C30") (pin "2") (pinfunction "2_2") (pintype "passive"))
      (node (ref "C31") (pin "2") (pinfunction "2_2") (pintype "passive"))
      (node (ref "C32") (pin "2") (pinfunction "2_2") (pintype "passive"))
      (node (ref "C33") (pin "2") (pinfunction "2_2") (pintype "passive"))
      (node (ref "C37") (pin "2") (pinfunction "2_2") (pintype "passive"))
      (node (ref "C38") (pin "2") (pinfunction "2_2") (pintype "passive"))
      (node (ref "C39") (pin "2") (pinfunction "2_2") (pintype "passive"))
      (node (ref "C4") (pin "2") (pinfunction "2_2") (pintype "passive"))
      (node (ref "C42") (pin "2") (pinfunction "2_2") (pintype "passive"))
      (node (ref "C43") (pin "2") (pinfunction "2_2") (pintype "passive"))
      (node (ref "C5") (pin "2") (pinfunction "2_2") (pintype "passive"))
      (node (ref "C6") (pin "2") (pinfunction "2_2") (pintype "passive"))
      (node (ref "C7") (pin "2") (pinfunction "2_2") (pintype "passive"))
      (node (ref "C8") (pin "2") (pinfunction "2_2") (pintype "passive"))
      (node (ref "C9") (pin "2") (pinfunction "2_2") (pintype "passive"))
      (node (ref "D1") (pin "2") (pinfunction "GND_2") (pintype "bidirectional"))
      (node (ref "D4") (pin "1") (pinfunction "K_1") (pintype "bidirectional"))
      (node (ref "EPD_C1") (pin "1") (pinfunction "1_1") (pintype "passive"))
      (node (ref "EPD_C10") (pin "1") (pinfunction "1_1") (pintype "passive"))
      (node (ref "EPD_C11") (pin "1") (pinfunction "1_1") (pintype "passive"))
      (node (ref "EPD_C12") (pin "1") (pinfunction "1_1") (pintype "passive"))
      (node (ref "EPD_C2") (pin "1") (pinfunction "1_1") (pintype "passive"))
      (node (ref "EPD_C5") (pin "1") (pinfunction "1_1") (pintype "passive"))
      (node (ref "EPD_C6") (pin "1") (pinfunction "1_1") (pintype "passive"))
      (node (ref "EPD_C7") (pin "1") (pinfunction "1_1") (pintype "passive"))
      (node (ref "EPD_C8") (pin "1") (pinfunction "1_1") (pintype "passive"))
      (node (ref "EPD_C9") (pin "1") (pinfunction "1_1") (pintype "passive"))
      (node (ref "IC1") (pin "D2") (pinfunction "GND_D2") (pintype "bidirectional"))
      (node (ref "IC2") (pin "B1") (pinfunction "IN/TRIG_B1") (pintype "bidirectional"))
      (node (ref "IC2") (pin "B3") (pinfunction "GND_B3") (pintype "bidirectional"))
      (node (ref "IC3") (pin "8") (pinfunction "GNDIO_8") (pintype "bidirectional"))
      (node (ref "IC3") (pin "9") (pinfunction "GND_9") (pintype "bidirectional"))
      (node (ref "IC9") (pin "B1") (pinfunction "VSEL_B1") (pintype "bidirectional"))
      (node (ref "IC9") (pin "C1") (pinfunction "AGND_C1") (pintype "bidirectional"))
      (node (ref "IC9") (pin "C2") (pinfunction "PGND_1_C2") (pintype "bidirectional"))
      (node (ref "IC9") (pin "C3") (pinfunction "PGND_2_C3") (pintype "bidirectional"))
      (node (ref "J1") (pin "17") (pinfunction "17_17") (pintype "bidirectional"))
      (node (ref "J1") (pin "8") (pinfunction "8_8") (pintype "bidirectional"))
      (node (ref "J1") (pin "MP1") (pinfunction "MP1_MP1") (pintype "bidirectional"))
      (node (ref "J1") (pin "MP2") (pinfunction "MP2_MP2") (pintype "bidirectional"))
      (node (ref "J2") (pin "3") (pinfunction "3_3") (pintype "bidirectional"))
      (node (ref "J2") (pin "5") (pinfunction "5_5") (pintype "bidirectional"))
      (node (ref "J4") (pin "A12_B1") (pinfunction "GND_A12_B1") (pintype "power_in"))
      (node (ref "J4") (pin "A1_B12") (pinfunction "GND_A1_B12") (pintype "power_in"))
      (node (ref "J4") (pin "SH1") (pinfunction "SHIELD_SH1") (pintype "passive"))
      (node (ref "J4") (pin "SH2") (pinfunction "SHIELD_SH2") (pintype "passive"))
      (node (ref "J4") (pin "SH3") (pinfunction "SHIELD_SH3") (pintype "passive"))
      (node (ref "J4") (pin "SH4") (pinfunction "SHIELD_SH4") (pintype "passive"))
      (node (ref "R1") (pin "1") (pinfunction "1_1") (pintype "bidirectional"))
      (node (ref "R1_USB") (pin "1") (pinfunction "1_1") (pintype "bidirectional"))
      (node (ref "R2_EP_DR") (pin "1") (pinfunction "1_1") (pintype "bidirectional"))
      (node (ref "R2_USB") (pin "2") (pinfunction "2_2") (pintype "bidirectional"))
      (node (ref "R3") (pin "1") (pinfunction "1_1") (pintype "bidirectional"))
      (node (ref "R_TYPE_SEL") (pin "1") (pinfunction "1_1") (pintype "bidirectional"))
      (node (ref "SJ1") (pin "1") (pinfunction "1_1") (pintype "passive"))
      (node (ref "SW_DN") (pin "1") (pinfunction "1_1") (pintype "passive"))
      (node (ref "SW_ENT") (pin "1") (pinfunction "1_1") (pintype "passive"))
      (node (ref "SW_UP") (pin "1") (pinfunction "1_1") (pintype "passive"))
      (node (ref "TP_BAT_GND") (pin "TP") (pinfunction "TP_TP") (pintype "input"))
      (node (ref "TP_GND") (pin "TP") (pinfunction "TP_TP") (pintype "input"))
      (node (ref "U$1") (pin "P$74") (pinfunction "VSS_PAD_P$74") (pintype "bidirectional"))
      (node (ref "U$1") (pin "P$75") (pinfunction "VSS_PAD_P$75") (pintype "bidirectional"))
      (node (ref "U$1") (pin "P$76") (pinfunction "VSS_PAD_P$76") (pintype "bidirectional"))
      (node (ref "U$1") (pin "P$77") (pinfunction "VSS_PAD_P$77") (pintype "bidirectional"))
      (node (ref "U$1") (pin "P$78") (pinfunction "VSS_PAD_P$78") (pintype "bidirectional"))
      (node (ref "U$1") (pin "P$79") (pinfunction "VSS_PAD_P$79") (pintype "bidirectional"))
      (node (ref "U$1") (pin "P$80") (pinfunction "VSS_PAD_P$80") (pintype "bidirectional"))
      (node (ref "U$1") (pin "P$81") (pinfunction "VSS_PAD_P$81") (pintype "bidirectional"))
      (node (ref "U$1") (pin "P$82") (pinfunction "VSS_PAD_P$82") (pintype "bidirectional"))
      (node (ref "U$1") (pin "P$83") (pinfunction "VSS_PAD_P$83") (pintype "bidirectional"))
      (node (ref "U$1") (pin "P$84") (pinfunction "VSS_PAD_P$84") (pintype "bidirectional"))
      (node (ref "U$1") (pin "P$85") (pinfunction "VSS_PAD_P$85") (pintype "bidirectional"))
      (node (ref "U$1") (pin "P$86") (pinfunction "VSS_PAD_P$86") (pintype "bidirectional"))
      (node (ref "U$1") (pin "P$87") (pinfunction "VSS_PAD_P$87") (pintype "bidirectional"))
      (node (ref "U$1") (pin "P$88") (pinfunction "VSS_PAD_P$88") (pintype "bidirectional"))
      (node (ref "U$1") (pin "P$89") (pinfunction "VSS_PAD_P$89") (pintype "bidirectional"))
      (node (ref "U$1") (pin "P$90") (pinfunction "VSS_PAD_P$90") (pintype "bidirectional"))
      (node (ref "U$1") (pin "P$B7") (pinfunction "VSS_P$B7") (pintype "power_in"))
      (node (ref "U$1") (pin "P$F23") (pinfunction "VSS_PA_P$F23") (pintype "bidirectional"))
      (node (ref "U$2") (pin "2") (pinfunction "2_2") (pintype "passive"))
      (node (ref "U3") (pin "1") (pinfunction "CTG_1") (pintype "power_in"))
      (node (ref "U3") (pin "4") (pinfunction "GND_4") (pintype "power_in"))
      (node (ref "U3") (pin "6") (pinfunction "QSTRT_6") (pintype "input"))
      (node (ref "U3") (pin "9") (pinfunction "EP_9") (pintype "power_in"))
      (node (ref "X1") (pin "2") (pinfunction "2_2") (pintype "passive"))
      (node (ref "X1") (pin "4") (pinfunction "4_4") (pintype "passive"))
    )
    (net (code "25") (name "HAPTIC_EN{slash}1.4C") (class "Default")
      (node (ref "IC2") (pin "A1") (pinfunction "EN_A1") (pintype "bidirectional"))
    )
    (net (code "26") (name "HAPTIC_EN{slash}2.6A") (class "Default")
      (node (ref "U$1") (pin "P$U1") (pinfunction "P0.12_P$U1") (pintype "bidirectional"))
    )
    (net (code "27") (name "IMU_INT1") (class "Default")
      (node (ref "IC3") (pin "5") (pinfunction "INT1_5") (pintype "bidirectional"))
      (node (ref "U$1") (pin "P$N1") (pinfunction "P0.08_P$N1") (pintype "bidirectional"))
    )
    (net (code "28") (name "IMU_INT2") (class "Default")
      (node (ref "IC3") (pin "6") (pinfunction "INT2_6") (pintype "bidirectional"))
      (node (ref "U$1") (pin "P$P2") (pinfunction "P1.08_P$P2") (pintype "bidirectional"))
    )
    (net (code "29") (name "LX1") (class "Default")
      (node (ref "IC9") (pin "B2") (pinfunction "SW1_1_B2") (pintype "bidirectional"))
      (node (ref "IC9") (pin "B3") (pinfunction "SW1_2_B3") (pintype "bidirectional"))
      (node (ref "L7") (pin "1") (pinfunction "1_1") (pintype "bidirectional"))
    )
    (net (code "30") (name "LX2") (class "Default")
      (node (ref "IC9") (pin "D2") (pinfunction "SW2_1_D2") (pintype "bidirectional"))
      (node (ref "IC9") (pin "D3") (pinfunction "SW2_2_D3") (pintype "bidirectional"))
      (node (ref "L7") (pin "2") (pinfunction "2_2") (pintype "bidirectional"))
    )
    (net (code "31") (name "MOSI{slash}1.5B") (class "Default")
      (node (ref "J1") (pin "14") (pinfunction "14_14") (pintype "bidirectional"))
    )
    (net (code "32") (name "MOSI{slash}2.2D") (class "Default")
      (node (ref "U$1") (pin "P$B13") (pinfunction "P0.03/AIN1_P$B13") (pintype "bidirectional"))
    )
    (net (code "33") (name "Net-(D2-K)") (class "Default")
      (node (ref "C2-EP-DR") (pin "1") (pinfunction "1_1") (pintype "passive"))
      (node (ref "D2") (pin "1") (pinfunction "K_1") (pintype "bidirectional"))
      (node (ref "D4") (pin "2") (pinfunction "A_2") (pintype "bidirectional"))
    )
    (net (code "34") (name "Net-(D5-A)") (class "Default")
      (node (ref "C2-EP-DR") (pin "2") (pinfunction "2_2") (pintype "passive"))
      (node (ref "D5") (pin "2") (pinfunction "A_2") (pintype "bidirectional"))
      (node (ref "L5") (pin "1") (pinfunction "1_1") (pintype "passive"))
      (node (ref "Q3") (pin "3") (pinfunction "D_3") (pintype "bidirectional"))
    )
    (net (code "35") (name "Net-(EPD_C1-Pad2)") (class "Default")
      (node (ref "EPD_C1") (pin "2") (pinfunction "2_2") (pintype "passive"))
      (node (ref "J1") (pin "5") (pinfunction "5_5") (pintype "bidirectional"))
    )
    (net (code "36") (name "Net-(EPD_C2-Pad2)") (class "Default")
      (node (ref "EPD_C2") (pin "2") (pinfunction "2_2") (pintype "passive"))
      (node (ref "J1") (pin "4") (pinfunction "4_4") (pintype "bidirectional"))
    )
    (net (code "37") (name "Net-(EPD_C6-Pad2)") (class "Default")
      (node (ref "EPD_C6") (pin "2") (pinfunction "2_2") (pintype "passive"))
      (node (ref "J1") (pin "18") (pinfunction "18_18") (pintype "bidirectional"))
    )
    (net (code "38") (name "Net-(EPD_C7-Pad2)") (class "Default")
      (node (ref "EPD_C7") (pin "2") (pinfunction "2_2") (pintype "passive"))
      (node (ref "J1") (pin "19") (pinfunction "19_19") (pintype "bidirectional"))
    )
    (net (code "39") (name "Net-(EPD_C8-Pad2)") (class "Default")
      (node (ref "EPD_C8") (pin "2") (pinfunction "2_2") (pintype "passive"))
      (node (ref "J1") (pin "20") (pinfunction "20_20") (pintype "bidirectional"))
    )
    (net (code "40") (name "Net-(EPD_C10-Pad2)") (class "Default")
      (node (ref "EPD_C10") (pin "2") (pinfunction "2_2") (pintype "passive"))
      (node (ref "J1") (pin "22") (pinfunction "22_22") (pintype "bidirectional"))
    )
    (net (code "41") (name "Net-(EPD_C12-Pad2)") (class "Default")
      (node (ref "EPD_C12") (pin "2") (pinfunction "2_2") (pintype "passive"))
      (node (ref "J1") (pin "24") (pinfunction "24_24") (pintype "bidirectional"))
    )
    (net (code "42") (name "Net-(IC1-TS{slash}MR)") (class "Default")
      (node (ref "IC1") (pin "D1") (pinfunction "TS/MR_D1") (pintype "bidirectional"))
      (node (ref "R1") (pin "2") (pinfunction "2_2") (pintype "bidirectional"))
    )
    (net (code "43") (name "Net-(IC2-REG)") (class "Default")
      (node (ref "C32") (pin "1") (pinfunction "1_1") (pintype "passive"))
      (node (ref "IC2") (pin "A2") (pinfunction "REG_A2") (pintype "bidirectional"))
    )
    (net (code "44") (name "Net-(IC3-SDO)") (class "Default")
      (node (ref "IC3") (pin "1") (pinfunction "SDO_1") (pintype "bidirectional"))
      (node (ref "R3") (pin "2") (pinfunction "2_2") (pintype "bidirectional"))
    )
    (net (code "45") (name "Net-(IC9-SCL)") (class "Default")
      (node (ref "IC9") (pin "D1") (pinfunction "SCL_D1") (pintype "bidirectional"))
      (node (ref "R4") (pin "2") (pinfunction "2_2") (pintype "bidirectional"))
    )
    (net (code "46") (name "Net-(IC9-SDA)") (class "Default")
      (node (ref "IC9") (pin "E1") (pinfunction "SDA_E1") (pintype "bidirectional"))
      (node (ref "R2") (pin "1") (pinfunction "1_1") (pintype "bidirectional"))
    )
    (net (code "47") (name "Net-(J4-CC1)") (class "Default")
      (node (ref "J4") (pin "A5") (pinfunction "CC1_A5") (pintype "bidirectional"))
      (node (ref "R1_USB") (pin "2") (pinfunction "2_2") (pintype "bidirectional"))
    )
    (net (code "48") (name "Net-(J4-CC2)") (class "Default")
      (node (ref "J4") (pin "B5") (pinfunction "CC2_B5") (pintype "bidirectional"))
      (node (ref "R2_USB") (pin "1") (pinfunction "1_1") (pintype "bidirectional"))
    )
    (net (code "49") (name "Net-(L2-Pad1)") (class "Default")
      (node (ref "L2") (pin "1") (pinfunction "1_1") (pintype "passive"))
      (node (ref "L3") (pin "2") (pinfunction "2_2") (pintype "passive"))
    )
    (net (code "50") (name "Net-(R1_EP_DR-Pad1)") (class "Default")
      (node (ref "R1_EP_DR") (pin "1") (pinfunction "1_1") (pintype "bidirectional"))
      (node (ref "R_TYPE_SEL") (pin "2") (pinfunction "2_2") (pintype "bidirectional"))
      (node (ref "SJ1") (pin "2") (pinfunction "2_2") (pintype "passive"))
    )
    (net (code "51") (name "Net-(U$1-ANT)") (class "Default")
      (node (ref "C3") (pin "1") (pinfunction "1_1") (pintype "passive"))
      (node (ref "L1") (pin "1") (pinfunction "1_1") (pintype "passive"))
      (node (ref "U$1") (pin "P$H23") (pinfunction "ANT_P$H23") (pintype "bidirectional"))
    )
    (net (code "52") (name "Net-(U$1-DCC)") (class "Default")
      (node (ref "L2") (pin "2") (pinfunction "2_2") (pintype "passive"))
      (node (ref "U$1") (pin "P$B3") (pinfunction "DCC_P$B3") (pintype "output"))
    )
    (net (code "53") (name "Net-(U$1-DEC2)") (class "Default")
      (node (ref "C13") (pin "1") (pinfunction "1_1") (pintype "passive"))
      (node (ref "U$1") (pin "P$A18") (pinfunction "DEC2_P$A18") (pintype "bidirectional"))
    )
    (net (code "54") (name "Net-(U$1-DEC3V3)") (class "Default")
      (node (ref "C20") (pin "1") (pinfunction "1_1") (pintype "passive"))
      (node (ref "U$1") (pin "P$AC5") (pinfunction "DEC3V3_P$AC5") (pintype "bidirectional"))
    )
    (net (code "55") (name "Net-(U$1-DEC5)") (class "Default")
      (node (ref "C9") (pin "1") (pinfunction "1_1") (pintype "passive"))
      (node (ref "U$1") (pin "P$N24") (pinfunction "DEC5_P$N24") (pintype "bidirectional"))
    )
    (net (code "56") (name "Net-(U$1-P0.00{slash}XL1)") (class "Default")
      (node (ref "C17") (pin "2") (pinfunction "2_2") (pintype "passive"))
      (node (ref "U$1") (pin "P$D2") (pinfunction "P0.00/XL1_P$D2") (pintype "bidirectional"))
      (node (ref "X2") (pin "1") (pinfunction "1_1") (pintype "passive"))
    )
    (net (code "57") (name "Net-(U$1-P0.01{slash}XL2)") (class "Default")
      (node (ref "C18") (pin "2") (pinfunction "2_2") (pintype "passive"))
      (node (ref "U$1") (pin "P$F2") (pinfunction "P0.01/XL2_P$F2") (pintype "bidirectional"))
      (node (ref "X2") (pin "2") (pinfunction "2_2") (pintype "passive"))
    )
    (net (code "58") (name "Net-(U$1-XC1)") (class "Default")
      (node (ref "C1") (pin "1") (pinfunction "1_1") (pintype "passive"))
      (node (ref "U$1") (pin "P$B24") (pinfunction "XC1_P$B24") (pintype "input"))
    )
    (net (code "59") (name "Net-(U$1-XC2)") (class "Default")
      (node (ref "C2") (pin "1") (pinfunction "1_1") (pintype "passive"))
      (node (ref "U$1") (pin "P$A23") (pinfunction "XC2_P$A23") (pintype "output"))
      (node (ref "X1") (pin "3") (pinfunction "3_3") (pintype "passive"))
    )
    (net (code "60") (name "OUT+") (class "Default")
      (node (ref "IC2") (pin "A3") (pinfunction "OUT+_A3") (pintype "bidirectional"))
      (node (ref "TP_OP") (pin "TP") (pinfunction "TP_TP") (pintype "input"))
    )
    (net (code "61") (name "OUT-") (class "Default")
      (node (ref "IC2") (pin "C3") (pinfunction "OUT-_C3") (pintype "bidirectional"))
      (node (ref "TP_ON") (pin "TP") (pinfunction "TP_TP") (pintype "input"))
    )
    (net (code "62") (name "P0.04") (class "Default")
      (node (ref "U$1") (pin "P$J1") (pinfunction "P0.04/AIN2_P$J1") (pintype "bidirectional"))
    )
    (net (code "63") (name "P0.09") (class "Default")
      (node (ref "U$1") (pin "P$L24") (pinfunction "P0.09/NFC1_P$L24") (pintype "bidirectional"))
    )
    (net (code "64") (name "P0.13{slash}1.5D") (class "Default")
      (node (ref "C30") (pin "1") (pinfunction "1_1") (pintype "passive"))
      (node (ref "R5") (pin "1") (pinfunction "1_1") (pintype "bidirectional"))
      (node (ref "SW_UP") (pin "2") (pinfunction "2_2") (pintype "passive"))
    )
    (net (code "65") (name "P0.13{slash}2.6C") (class "Default")
      (node (ref "U$1") (pin "P$AD8") (pinfunction "P0.13_P$AD8") (pintype "bidirectional"))
    )
    (net (code "66") (name "P0.14{slash}1.5D") (class "Default")
      (node (ref "C31") (pin "1") (pinfunction "1_1") (pintype "passive"))
      (node (ref "R8") (pin "1") (pinfunction "1_1") (pintype "bidirectional"))
      (node (ref "SW_ENT") (pin "2") (pinfunction "2_2") (pintype "passive"))
    )
    (net (code "67") (name "P0.14{slash}2.7C") (class "Default")
      (node (ref "U$1") (pin "P$AC9") (pinfunction "P0.14_P$AC9") (pintype "bidirectional"))
    )
    (net (code "68") (name "P0.19") (class "Default")
      (node (ref "U$1") (pin "P$AC15") (pinfunction "P0.19_P$AC15") (pintype "bidirectional"))
    )
    (net (code "69") (name "P0.20") (class "Default")
      (node (ref "U$1") (pin "P$AD16") (pinfunction "P0.20_P$AD16") (pintype "bidirectional"))
    )
    (net (code "70") (name "P0.21") (class "Default")
      (node (ref "U$1") (pin "P$AC17") (pinfunction "P0.21_P$AC17") (pintype "bidirectional"))
    )
    (net (code "71") (name "P0.22") (class "Default")
      (node (ref "U$1") (pin "P$AD18") (pinfunction "P0.22_P$AD18") (pintype "bidirectional"))
    )
    (net (code "72") (name "P0.23") (class "Default")
      (node (ref "U$1") (pin "P$AC19") (pinfunction "P0.23_P$AC19") (pintype "bidirectional"))
    )
    (net (code "73") (name "P0.24") (class "Default")
      (node (ref "U$1") (pin "P$AD20") (pinfunction "P0.24_P$AD20") (pintype "bidirectional"))
    )
    (net (code "74") (name "P0.25") (class "Default")
      (node (ref "U$1") (pin "P$AC21") (pinfunction "P0.25_P$AC21") (pintype "bidirectional"))
    )
    (net (code "75") (name "P0.26") (class "Default")
      (node (ref "U$1") (pin "P$G1") (pinfunction "P0.26_P$G1") (pintype "bidirectional"))
    )
    (net (code "76") (name "P0.27") (class "Default")
      (node (ref "U$1") (pin "P$H2") (pinfunction "P0.27_P$H2") (pintype "bidirectional"))
    )
    (net (code "77") (name "P0.28") (class "Default")
      (node (ref "U$1") (pin "P$B11") (pinfunction "P0.28/AIN4_P$B11") (pintype "bidirectional"))
    )
    (net (code "78") (name "P0.29") (class "Default")
      (node (ref "U$1") (pin "P$A10") (pinfunction "P0.29/AIN5_P$A10") (pintype "bidirectional"))
    )
    (net (code "79") (name "P0.30") (class "Default")
      (node (ref "U$1") (pin "P$B9") (pinfunction "P0.30/AIN6_P$B9") (pintype "bidirectional"))
    )
    (net (code "80") (name "P0.31") (class "Default")
      (node (ref "U$1") (pin "P$A8") (pinfunction "P0.31/AIN7_P$A8") (pintype "bidirectional"))
    )
    (net (code "81") (name "P1.01{slash}1.6C") (class "Default")
      (node (ref "Q1") (pin "1") (pinfunction "G_1") (pintype "bidirectional"))
      (node (ref "R_PWR_EPD") (pin "1") (pinfunction "1_1") (pintype "bidirectional"))
    )
    (net (code "82") (name "P1.01{slash}2.4B") (class "Default")
      (node (ref "U$1") (pin "P$Y23") (pinfunction "P1.01_P$Y23") (pintype "bidirectional"))
    )
    (net (code "83") (name "P1.02{slash}1.6C") (class "Default")
      (node (ref "C29") (pin "1") (pinfunction "1_1") (pintype "passive"))
      (node (ref "R7") (pin "1") (pinfunction "1_1") (pintype "bidirectional"))
      (node (ref "SW_DN") (pin "2") (pinfunction "2_2") (pintype "passive"))
    )
    (net (code "84") (name "P1.02{slash}2.8C") (class "Default")
      (node (ref "U$1") (pin "P$W24") (pinfunction "P1.02_P$W24") (pintype "bidirectional"))
    )
    (net (code "85") (name "P1.03") (class "Default")
      (node (ref "U$1") (pin "P$V23") (pinfunction "P1.03_P$V23") (pintype "bidirectional"))
    )
    (net (code "86") (name "P1.04") (class "Default")
      (node (ref "U$1") (pin "P$U24") (pinfunction "P1.04_P$U24") (pintype "bidirectional"))
    )
    (net (code "87") (name "P1.05") (class "Default")
      (node (ref "U$1") (pin "P$T23") (pinfunction "P1.05_P$T23") (pintype "bidirectional"))
    )
    (net (code "88") (name "P1.06") (class "Default")
      (node (ref "U$1") (pin "P$R24") (pinfunction "P1.06_P$R24") (pintype "bidirectional"))
    )
    (net (code "89") (name "P1.07") (class "Default")
      (node (ref "U$1") (pin "P$P23") (pinfunction "P1.07_P$P23") (pintype "bidirectional"))
    )
    (net (code "90") (name "P1.09") (class "Default")
      (node (ref "U$1") (pin "P$R1") (pinfunction "P1.09_P$R1") (pintype "bidirectional"))
    )
    (net (code "91") (name "P1.10") (class "Default")
      (node (ref "U$1") (pin "P$A20") (pinfunction "P1.10_P$A20") (pintype "bidirectional"))
    )
    (net (code "92") (name "P1.11") (class "Default")
      (node (ref "U$1") (pin "P$B19") (pinfunction "P1.11_P$B19") (pintype "bidirectional"))
    )
    (net (code "93") (name "P1.12") (class "Default")
      (node (ref "U$1") (pin "P$B17") (pinfunction "P1.12_P$B17") (pintype "bidirectional"))
    )
    (net (code "94") (name "P1.13") (class "Default")
      (node (ref "U$1") (pin "P$A16") (pinfunction "P1.13_P$A16") (pintype "bidirectional"))
    )
    (net (code "95") (name "P1.14") (class "Default")
      (node (ref "U$1") (pin "P$B15") (pinfunction "P1.14_P$B15") (pintype "bidirectional"))
    )
    (net (code "96") (name "P1.15") (class "Default")
      (node (ref "U$1") (pin "P$A14") (pinfunction "P1.15_P$A14") (pintype "bidirectional"))
    )
    (net (code "97") (name "PMIC_INT") (class "Default")
      (node (ref "IC1") (pin "A1") (pinfunction "~{INT}_A1") (pintype "bidirectional"))
      (node (ref "U$1") (pin "P$T2") (pinfunction "P0.11_P$T2") (pintype "bidirectional"))
    )
    (net (code "98") (name "PREVGH") (class "Default")
      (node (ref "D5") (pin "1") (pinfunction "K_1") (pintype "bidirectional"))
      (node (ref "EPD_C9") (pin "2") (pinfunction "2_2") (pintype "passive"))
      (node (ref "J1") (pin "21") (pinfunction "21_21") (pintype "bidirectional"))
    )
    (net (code "99") (name "PREVGL") (class "Default")
      (node (ref "D2") (pin "2") (pinfunction "A_2") (pintype "bidirectional"))
      (node (ref "EPD_C11") (pin "2") (pinfunction "2_2") (pintype "passive"))
      (node (ref "J1") (pin "23") (pinfunction "23_23") (pintype "bidirectional"))
    )
    (net (code "100") (name "RESE") (class "Default")
      (node (ref "J1") (pin "3") (pinfunction "3_3") (pintype "bidirectional"))
      (node (ref "Q3") (pin "2") (pinfunction "S_2") (pintype "bidirectional"))
      (node (ref "R1_EP_DR") (pin "2") (pinfunction "2_2") (pintype "bidirectional"))
    )
    (net (code "101") (name "RESET") (class "Default")
      (node (ref "J2") (pin "6") (pinfunction "6_6") (pintype "bidirectional"))
      (node (ref "TP_RESET") (pin "TP") (pinfunction "TP_TP") (pintype "input"))
      (node (ref "U$1") (pin "P$AC13") (pinfunction "P0.18/RESET_P$AC13") (pintype "bidirectional"))
    )
    (net (code "102") (name "RF") (class "Default")
      (node (ref "ANT1") (pin "1") (pinfunction "FEED_1") (pintype "input"))
      (node (ref "C22") (pin "1") (pinfunction "1_1") (pintype "passive"))
      (node (ref "C4") (pin "1") (pinfunction "1_1") (pintype "passive"))
      (node (ref "L1") (pin "2") (pinfunction "2_2") (pintype "passive"))
    )
    (net (code "103") (name "SCK{slash}1.5B") (class "Default")
      (node (ref "J1") (pin "13") (pinfunction "13_13") (pintype "bidirectional"))
    )
    (net (code "104") (name "SCK{slash}2.2D") (class "Default")
      (node (ref "U$1") (pin "P$A12") (pinfunction "P0.02/AIN0_P$A12") (pintype "bidirectional"))
    )
    (net (code "105") (name "SCL{slash}1.4C") (class "Default")
      (node (ref "IC2") (pin "C1") (pinfunction "SCL_C1") (pintype "bidirectional"))
      (node (ref "U3") (pin "7") (pinfunction "SCL_7") (pintype "input"))
    )
    (net (code "106") (name "SCL{slash}2.4C") (class "Default")
      (node (ref "IC1") (pin "B1") (pinfunction "SCL_B1") (pintype "bidirectional"))
      (node (ref "IC3") (pin "12") (pinfunction "SCX_12") (pintype "bidirectional"))
      (node (ref "R17") (pin "2") (pinfunction "2_2") (pintype "bidirectional"))
      (node (ref "R4") (pin "1") (pinfunction "1_1") (pintype "bidirectional"))
      (node (ref "TP_SCL") (pin "TP") (pinfunction "TP_TP") (pintype "input"))
      (node (ref "U$1") (pin "P$M2") (pinfunction "P0.07_P$M2") (pintype "bidirectional"))
    )
    (net (code "107") (name "SDA{slash}1.4C") (class "Default")
      (node (ref "IC2") (pin "B2") (pinfunction "SDA_B2") (pintype "bidirectional"))
      (node (ref "U3") (pin "8") (pinfunction "SDA_8") (pintype "bidirectional"))
    )
    (net (code "108") (name "SDA{slash}2.4C") (class "Default")
      (node (ref "IC1") (pin "C1") (pinfunction "SDA_C1") (pintype "bidirectional"))
      (node (ref "IC3") (pin "2") (pinfunction "SDX_2") (pintype "bidirectional"))
      (node (ref "R18") (pin "2") (pinfunction "2_2") (pintype "bidirectional"))
      (node (ref "R2") (pin "2") (pinfunction "2_2") (pintype "bidirectional"))
      (node (ref "TP_SDA") (pin "TP") (pinfunction "TP_TP") (pintype "input"))
      (node (ref "U$1") (pin "P$L1") (pinfunction "P0.06_P$L1") (pintype "bidirectional"))
    )
    (net (code "109") (name "SWDCLK") (class "Default")
      (node (ref "J2") (pin "4") (pinfunction "4_4") (pintype "bidirectional"))
      (node (ref "TP_SWDCLK") (pin "TP") (pinfunction "TP_TP") (pintype "input"))
      (node (ref "U$1") (pin "P$AA24") (pinfunction "SWDCLK_P$AA24") (pintype "input"))
    )
    (net (code "110") (name "SWDIO") (class "Default")
      (node (ref "J2") (pin "2") (pinfunction "2_2") (pintype "bidirectional"))
      (node (ref "TP_SWDIO") (pin "TP") (pinfunction "TP_TP") (pintype "input"))
      (node (ref "U$1") (pin "P$AC24") (pinfunction "SWDIO_P$AC24") (pintype "bidirectional"))
    )
    (net (code "111") (name "SWO") (class "Default")
      (node (ref "TP_SWO") (pin "TP") (pinfunction "TP_TP") (pintype "input"))
      (node (ref "U$1") (pin "P$AD22") (pinfunction "P1.00_P$AD22") (pintype "bidirectional"))
    )
    (net (code "112") (name "VBAT{slash}1.2A") (class "Default")
      (node (ref "C27") (pin "1") (pinfunction "1_1") (pintype "passive"))
      (node (ref "TP_VBAT") (pin "TP") (pinfunction "TP_TP") (pintype "input"))
      (node (ref "U3") (pin "2") (pinfunction "CELL_2") (pintype "power_in"))
      (node (ref "U3") (pin "3") (pinfunction "VDD_3") (pintype "power_in"))
    )
    (net (code "113") (name "VBAT{slash}2.5C") (class "Default")
      (node (ref "C37") (pin "1") (pinfunction "1_1") (pintype "passive"))
      (node (ref "IC1") (pin "C2") (pinfunction "BAT_C2") (pintype "bidirectional"))
    )
    (net (code "114") (name "VBUS{slash}1.5D") (class "Default")
      (node (ref "C42") (pin "1") (pinfunction "1_1") (pintype "passive"))
      (node (ref "C43") (pin "1") (pinfunction "1_1") (pintype "passive"))
      (node (ref "D1") (pin "5") (pinfunction "VBUS_5") (pintype "bidirectional"))
      (node (ref "J4") (pin "A4_B9") (pinfunction "VBUS_A4_B9") (pintype "power_in"))
      (node (ref "J4") (pin "A9_B4") (pinfunction "VBUS_A9_B4") (pintype "power_in"))
    )
    (net (code "115") (name "VBUS{slash}2.6D") (class "Default")
      (node (ref "C38") (pin "1") (pinfunction "1_1") (pintype "passive"))
      (node (ref "IC1") (pin "A2") (pinfunction "IN_A2") (pintype "bidirectional"))
      (node (ref "U$1") (pin "P$AD2") (pinfunction "VBUS_P$AD2") (pintype "power_in"))
      (node (ref "U$2") (pin "1") (pinfunction "1_1") (pintype "passive"))
    )
    (net (code "116") (name "VREG") (class "Default")
      (node (ref "C23") (pin "2") (pinfunction "2_2") (pintype "passive"))
      (node (ref "C24") (pin "2") (pinfunction "2_2") (pintype "passive"))
      (node (ref "C39") (pin "1") (pinfunction "1_1") (pintype "passive"))
      (node (ref "IC1") (pin "B2") (pinfunction "SYS_B2") (pintype "bidirectional"))
      (node (ref "IC9") (pin "A1") (pinfunction "EN_A1") (pintype "bidirectional"))
      (node (ref "IC9") (pin "A2") (pinfunction "VIN_1_A2") (pintype "bidirectional"))
      (node (ref "IC9") (pin "A3") (pinfunction "VIN_2_A3") (pintype "bidirectional"))
      (node (ref "TP_VREG") (pin "TP") (pinfunction "TP_TP") (pintype "input"))
    )
    (net (code "117") (name "unconnected-(ANT1-NC-Pad2)") (class "Default")
      (node (ref "ANT1") (pin "2") (pinfunction "NC_2") (pintype "no_connect"))
    )
    (net (code "118") (name "unconnected-(C34-Pad2)") (class "Default")
      (node (ref "C34") (pin "2") (pinfunction "2_2") (pintype "passive"))
    )
    (net (code "119") (name "unconnected-(IC3-ASCL-Pad11)") (class "Default")
      (node (ref "IC3") (pin "11") (pinfunction "ASCL_11") (pintype "bidirectional"))
    )
    (net (code "120") (name "unconnected-(IC3-ASDA-Pad4)") (class "Default")
      (node (ref "IC3") (pin "4") (pinfunction "ASDA_4") (pintype "bidirectional"))
    )
    (net (code "121") (name "unconnected-(J1-Pad1)") (class "Default")
      (node (ref "J1") (pin "1") (pinfunction "1_1") (pintype "bidirectional"))
    )
    (net (code "122") (name "unconnected-(J1-Pad6)") (class "Default")
      (node (ref "J1") (pin "6") (pinfunction "6_6") (pintype "bidirectional"))
    )
    (net (code "123") (name "unconnected-(J1-Pad7)") (class "Default")
      (node (ref "J1") (pin "7") (pinfunction "7_7") (pintype "bidirectional"))
    )
    (net (code "124") (name "unconnected-(J4-SBU1-PadA8)") (class "Default")
      (node (ref "J4") (pin "A8") (pinfunction "SBU1_A8") (pintype "bidirectional"))
    )
    (net (code "125") (name "unconnected-(J4-SBU2-PadB8)") (class "Default")
      (node (ref "J4") (pin "B8") (pinfunction "SBU2_B8") (pintype "bidirectional"))
    )
    (net (code "126") (name "unconnected-(U$1-DCCH-PadP$AB2)") (class "Default")
      (node (ref "U$1") (pin "P$AB2") (pinfunction "DCCH_P$AB2") (pintype "bidirectional"))
    )
    (net (code "127") (name "unconnected-(X1-Pad1)") (class "Default")
      (node (ref "X1") (pin "1") (pinfunction "1_1") (pintype "passive"))
    )
  )
)
